# Peripheral_Circuit_A.net
KiCad netlist of a schematic drawn in Altium Designer
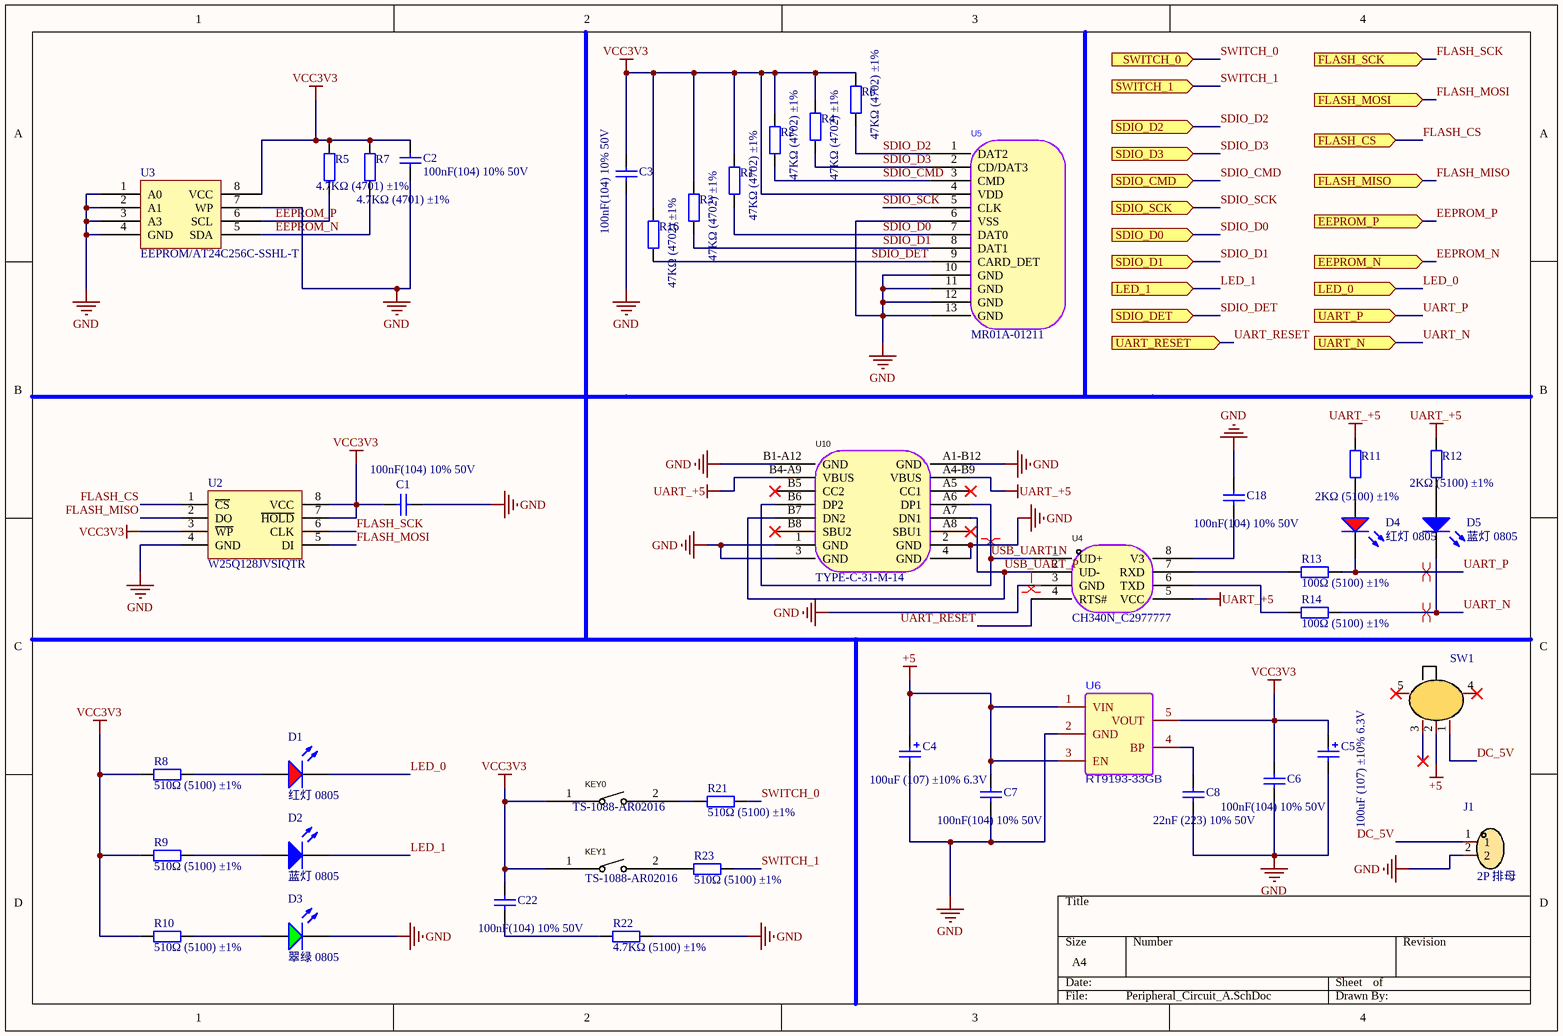
[diagram p0: Peripheral_Circuit_A.SchDoc]

(export (version "E")
  (design (tool "Eeschema 10.0.6"))
  (components
    (comp (ref "C1")
      (value "100nF(104) 10% 50V")
      (footprint "0805_C")
      (description "贴片电容")
      (libsource (lib "Miscellaneous Devices LC") (part "0805 100nF(104) 10% 50V"))
    )
    (comp (ref "C2")
      (value "100nF(104) 10% 50V")
      (footprint "0805_C")
      (description "贴片电容")
      (libsource (lib "Miscellaneous Devices LC") (part "0805 100nF(104) 10% 50V"))
    )
    (comp (ref "C3")
      (value "100nF(104) 10% 50V")
      (footprint "0805_C")
      (description "贴片电容")
      (libsource (lib "Miscellaneous Devices LC") (part "0805 100nF(104) 10% 50V"))
    )
    (comp (ref "C4")
      (value "100uF (107) ±10% 6.3V")
      (footprint "CASE-B_3528")
      (description "钽电容")
      (libsource (lib "Miscellaneous Devices LC") (part "3528 100uF (107) 10% 6.3V"))
    )
    (comp (ref "C5")
      (value "100uF (107) ±10% 6.3V")
      (footprint "CASE-B_3528")
      (description "钽电容")
      (libsource (lib "Miscellaneous Devices LC") (part "3528 100uF (107) 10% 6.3V"))
    )
    (comp (ref "C6")
      (value "100nF(104) 10% 50V")
      (footprint "0805_C")
      (description "贴片电容")
      (libsource (lib "Miscellaneous Devices LC") (part "0805 100nF(104) 10% 50V"))
    )
    (comp (ref "C7")
      (value "100nF(104) 10% 50V")
      (footprint "0805_C")
      (description "贴片电容")
      (libsource (lib "Miscellaneous Devices LC") (part "0805 100nF(104) 10% 50V"))
    )
    (comp (ref "C8")
      (value "22nF (223) 10% 50V")
      (footprint "0805_C")
      (description "贴片电容")
      (libsource (lib "Miscellaneous Devices LC") (part "0805 22nF (223) 10% 50V"))
    )
    (comp (ref "C18")
      (value "100nF(104) 10% 50V")
      (footprint "0805_C")
      (description "贴片电容")
      (libsource (lib "Miscellaneous Devices LC") (part "0805 100nF(104) 10% 50V"))
    )
    (comp (ref "C22")
      (value "100nF(104) 10% 50V")
      (footprint "0805_C")
      (description "贴片电容")
      (libsource (lib "Miscellaneous Devices LC") (part "0805 100nF(104) 10% 50V"))
    )
    (comp (ref "D1")
      (value "红灯 0805")
      (footprint "0805_LED_S1")
      (description "发光二极管")
      (libsource (lib "LED") (part "0805 红灯"))
    )
    (comp (ref "D2")
      (value "蓝灯 0805")
      (footprint "0805_LED_S1")
      (description "发光二极管")
      (libsource (lib "LED") (part "0805 蓝灯"))
    )
    (comp (ref "D3")
      (value "翠绿 0805")
      (footprint "0805_LED_S1")
      (description "发光二极管")
      (libsource (lib "LED") (part "0805 翠绿"))
    )
    (comp (ref "D4")
      (value "红灯 0805")
      (footprint "0805_LED_S1")
      (description "发光二极管")
      (libsource (lib "LED") (part "0805 红灯"))
    )
    (comp (ref "D5")
      (value "蓝灯 0805")
      (footprint "0805_LED_S1")
      (description "发光二极管")
      (libsource (lib "LED") (part "0805 蓝灯"))
    )
    (comp (ref "J1")
      (value "2P 排母")
      (footprint "PM254-1-02-W-8.5")
      (description "2p弯针")
      (fields
        (field (name "MANUFACTURER") "HCTL(华灿天禄)")
        (field (name "MANUFACTURER PART") "PM254-1-02-W-8.5")
      )
      (libsource (lib "EXTRA") (part "PM254-1-02-W-8.5"))
    )
    (comp (ref "KEY0")
      (value "TS-1088-AR02016")
      (footprint "SW-SMD_L3.9-W3.0-P4.45")
      (description "轻触开关")
      (fields (field (name "MANUFACTURER") "XUNPU(讯普)"))
      (libsource (lib "EXTRA") (part "TS-1088-AR02016"))
    )
    (comp (ref "KEY1")
      (value "TS-1088-AR02016")
      (footprint "SW-SMD_L3.9-W3.0-P4.45")
      (description "轻触开关")
      (fields (field (name "MANUFACTURER") "XUNPU(讯普)"))
      (libsource (lib "EXTRA") (part "TS-1088-AR02016"))
    )
    (comp (ref "R1")
      (value "47KΩ (4702) ±1%")
      (footprint "0805_R")
      (description "贴片电阻")
      (libsource (lib "Miscellaneous Devices LC") (part "0805 47KΩ (4702) 1%"))
    )
    (comp (ref "R2")
      (value "47KΩ (4702) ±1%")
      (footprint "0805_R")
      (description "贴片电阻")
      (libsource (lib "Miscellaneous Devices LC") (part "0805 47KΩ (4702) 1%"))
    )
    (comp (ref "R3")
      (value "47KΩ (4702) ±1%")
      (footprint "0805_R")
      (description "贴片电阻")
      (libsource (lib "Miscellaneous Devices LC") (part "0805 47KΩ (4702) 1%"))
    )
    (comp (ref "R4")
      (value "47KΩ (4702) ±1%")
      (footprint "0805_R")
      (description "贴片电阻")
      (libsource (lib "Miscellaneous Devices LC") (part "0805 47KΩ (4702) 1%"))
    )
    (comp (ref "R5")
      (value "4.7KΩ (4701) ±1%")
      (footprint "0805_R")
      (description "贴片电阻")
      (libsource (lib "Miscellaneous Devices LC") (part "0805 4.7KΩ (4701) 1%"))
    )
    (comp (ref "R6")
      (value "47KΩ (4702) ±1%")
      (footprint "0805_R")
      (description "贴片电阻")
      (libsource (lib "Miscellaneous Devices LC") (part "0805 47KΩ (4702) 1%"))
    )
    (comp (ref "R7")
      (value "4.7KΩ (4701) ±1%")
      (footprint "0805_R")
      (description "贴片电阻")
      (libsource (lib "Miscellaneous Devices LC") (part "0805 4.7KΩ (4701) 1%"))
    )
    (comp (ref "R8")
      (value "510Ω (5100) ±1%")
      (footprint "0805_R")
      (description "贴片电阻")
      (libsource (lib "Miscellaneous Devices LC") (part "0805 510Ω (5100) 1%"))
    )
    (comp (ref "R9")
      (value "510Ω (5100) ±1%")
      (footprint "0805_R")
      (description "贴片电阻")
      (libsource (lib "Miscellaneous Devices LC") (part "0805 510Ω (5100) 1%"))
    )
    (comp (ref "R10")
      (value "510Ω (5100) ±1%")
      (footprint "0805_R")
      (description "贴片电阻")
      (libsource (lib "Miscellaneous Devices LC") (part "0805 510Ω (5100) 1%"))
    )
    (comp (ref "R11")
      (value "2KΩ (5100) ±1%")
      (footprint "0805_R")
      (description "贴片电阻")
      (libsource (lib "") (part "0805 510Ω (5100) 1%_2"))
    )
    (comp (ref "R12")
      (value "2KΩ (5100) ±1%")
      (footprint "0805_R")
      (description "贴片电阻")
      (libsource (lib "") (part "0805 510Ω (5100) 1%_2"))
    )
    (comp (ref "R13")
      (value "100Ω (5100) ±1%")
      (footprint "0805_R")
      (description "贴片电阻")
      (libsource (lib "Miscellaneous Devices LC") (part "0805 510Ω (5100) 1%"))
    )
    (comp (ref "R14")
      (value "100Ω (5100) ±1%")
      (footprint "0805_R")
      (description "贴片电阻")
      (libsource (lib "Miscellaneous Devices LC") (part "0805 510Ω (5100) 1%"))
    )
    (comp (ref "R16")
      (value "47KΩ (4702) ±1%")
      (footprint "0805_R")
      (description "贴片电阻")
      (libsource (lib "Miscellaneous Devices LC") (part "0805 47KΩ (4702) 1%"))
    )
    (comp (ref "R21")
      (value "510Ω (5100) ±1%")
      (footprint "0805_R")
      (description "贴片电阻")
      (libsource (lib "Miscellaneous Devices LC") (part "0805 510Ω (5100) 1%"))
    )
    (comp (ref "R22")
      (value "4.7KΩ (5100) ±1%")
      (footprint "0805_R")
      (description "贴片电阻")
      (libsource (lib "") (part "0805 510Ω (5100) 1%_1"))
    )
    (comp (ref "R23")
      (value "510Ω (5100) ±1%")
      (footprint "0805_R")
      (description "贴片电阻")
      (libsource (lib "Miscellaneous Devices LC") (part "0805 510Ω (5100) 1%"))
    )
    (comp (ref "SW1")
      (value "SS12D07VG3 087")
      (footprint "SS12D07VG3")
      (description "直插贴片开关")
      (fields (field (name "MANUFACTURER") "SHOU HAN(首韩)"))
      (libsource (lib "EXTRA") (part "SS12D07VG3 087"))
    )
    (comp (ref "U2")
      (value "W25Q128JVSIQTR")
      (footprint "CH340_N")
      (description "Flash ROM")
      (libsource (lib "IC") (part "W25Q128JVSIQTR_[C97521]"))
    )
    (comp (ref "U3")
      (value "EEPROM/AT24C256C-SSHL-T")
      (footprint "CH340_N")
      (description "EEPROM")
      (libsource (lib "IC") (part "EEPROM/AT24C256C-SSHL-T_[C6482]"))
    )
    (comp (ref "U4")
      (value "CH340N_C2977777")
      (footprint "CH340_N")
      (description "TTL串口phy")
      (fields (field (name "DESIGNER") "U?"))
      (libsource (lib "EXTRA") (part "CH340N_C2977777"))
    )
    (comp (ref "U5")
      (value "MR01A-01211")
      (footprint "TF-SMD_MR01A-01211")
      (fields (field (name "MANUFACTURER") "ATOM(爱特姆)"))
      (libsource (lib "EXTRA") (part "MR01A-01211"))
    )
    (comp (ref "U6")
      (value "RT9193-33GB")
      (footprint "RT9193-33GB")
      (libsource (lib "EXTRA") (part "RT9193-33GB"))
    )
    (comp (ref "U10")
      (value "TYPE-C-31-M-14")
      (footprint "TYPE-C-31-M-14")
      (description "type-c接口")
      (fields (field (name "MANUFACTURER") "韩国韩荣"))
      (libsource (lib "EXTRA") (part "TYPE-C-31-M-14_1"))
    )
  )
  (nets
    (net (code "1") (name "+5") (class "Default")
      (node (ref "C4") (pin "1") (pinfunction "1_1") (pintype "passive"))
      (node (ref "C7") (pin "2") (pinfunction "2_2") (pintype "passive"))
      (node (ref "SW1") (pin "2") (pinfunction "2_2") (pintype "passive"))
      (node (ref "U6") (pin "1") (pinfunction "VIN_1") (pintype "passive"))
      (node (ref "U6") (pin "3") (pinfunction "EN_3") (pintype "passive"))
    )
    (net (code "2") (name "/DC_5V") (class "Default")
      (node (ref "J1") (pin "1") (pinfunction "1_1") (pintype "passive"))
      (node (ref "SW1") (pin "1") (pinfunction "1_1") (pintype "passive"))
    )
    (net (code "3") (name "/EEPROM_N") (class "Default")
      (node (ref "R7") (pin "1") (pinfunction "1_1") (pintype "passive"))
      (node (ref "U3") (pin "5") (pinfunction "SDA_5") (pintype "passive"))
    )
    (net (code "4") (name "/EEPROM_P") (class "Default")
      (node (ref "R5") (pin "1") (pinfunction "1_1") (pintype "passive"))
      (node (ref "U3") (pin "6") (pinfunction "SCL_6") (pintype "passive"))
    )
    (net (code "5") (name "/FLASH_CS") (class "Default")
      (node (ref "U2") (pin "1") (pinfunction "~{CS}_1") (pintype "passive"))
    )
    (net (code "6") (name "/FLASH_MISO") (class "Default")
      (node (ref "U2") (pin "2") (pinfunction "DO_2") (pintype "passive"))
    )
    (net (code "7") (name "/FLASH_MOSI") (class "Default")
      (node (ref "U2") (pin "5") (pinfunction "DI_5") (pintype "passive"))
    )
    (net (code "8") (name "/FLASH_SCK") (class "Default")
      (node (ref "U2") (pin "6") (pinfunction "CLK_6") (pintype "passive"))
    )
    (net (code "9") (name "/LED_0") (class "Default")
      (node (ref "D1") (pin "K") (pinfunction "K_K") (pintype "passive"))
    )
    (net (code "10") (name "/LED_1") (class "Default")
      (node (ref "D2") (pin "K") (pinfunction "K_K") (pintype "passive"))
    )
    (net (code "11") (name "/SDIO_CMD") (class "Default")
      (node (ref "R2") (pin "1") (pinfunction "1_1") (pintype "passive"))
      (node (ref "U5") (pin "3") (pinfunction "CMD_3") (pintype "passive"))
    )
    (net (code "12") (name "/SDIO_D0") (class "Default")
      (node (ref "R1") (pin "1") (pinfunction "1_1") (pintype "passive"))
      (node (ref "U5") (pin "7") (pinfunction "DAT0_7") (pintype "passive"))
    )
    (net (code "13") (name "/SDIO_D1") (class "Default")
      (node (ref "R3") (pin "1") (pinfunction "1_1") (pintype "passive"))
      (node (ref "U5") (pin "8") (pinfunction "DAT1_8") (pintype "passive"))
    )
    (net (code "14") (name "/SDIO_D2") (class "Default")
      (node (ref "R6") (pin "1") (pinfunction "1_1") (pintype "passive"))
      (node (ref "U5") (pin "1") (pinfunction "DAT2_1") (pintype "passive"))
    )
    (net (code "15") (name "/SDIO_D3") (class "Default")
      (node (ref "R4") (pin "1") (pinfunction "1_1") (pintype "passive"))
      (node (ref "U5") (pin "2") (pinfunction "CD/DAT3_2") (pintype "passive"))
    )
    (net (code "16") (name "/SDIO_DET") (class "Default")
      (node (ref "R16") (pin "1") (pinfunction "1_1") (pintype "passive"))
      (node (ref "U5") (pin "9") (pinfunction "CARD_DET_9") (pintype "passive"))
    )
    (net (code "17") (name "/SDIO_SCK") (class "Default")
      (node (ref "U5") (pin "5") (pinfunction "CLK_5") (pintype "passive"))
    )
    (net (code "18") (name "/SWITCH_0") (class "Default")
      (node (ref "R21") (pin "2") (pinfunction "2_2") (pintype "passive"))
    )
    (net (code "19") (name "/SWITCH_1") (class "Default")
      (node (ref "R23") (pin "2") (pinfunction "2_2") (pintype "passive"))
    )
    (net (code "20") (name "/UART_N") (class "Default")
      (node (ref "D5") (pin "K") (pinfunction "K_K") (pintype "passive"))
      (node (ref "R14") (pin "2") (pinfunction "2_2") (pintype "passive"))
    )
    (net (code "21") (name "/UART_P") (class "Default")
      (node (ref "D4") (pin "K") (pinfunction "K_K") (pintype "passive"))
      (node (ref "R13") (pin "2") (pinfunction "2_2") (pintype "passive"))
    )
    (net (code "22") (name "/UART_RESET") (class "Default")
      (node (ref "U4") (pin "4") (pinfunction "RTS#_4") (pintype "passive"))
    )
    (net (code "23") (name "/USB_UART_N") (class "Default")
      (node (ref "U10") (pin "A6") (pinfunction "DP1_A6") (pintype "passive"))
      (node (ref "U10") (pin "B6") (pinfunction "DP2_B6") (pintype "passive"))
      (node (ref "U4") (pin "1") (pinfunction "UD+_1") (pintype "passive"))
    )
    (net (code "24") (name "/USB_UART_P") (class "Default")
      (node (ref "U10") (pin "A7") (pinfunction "DN1_A7") (pintype "passive"))
      (node (ref "U10") (pin "B7") (pinfunction "DN2_B7") (pintype "passive"))
      (node (ref "U4") (pin "2") (pinfunction "UD-_2") (pintype "passive"))
    )
    (net (code "25") (name "GND") (class "Default")
      (node (ref "C1") (pin "2") (pinfunction "2_2") (pintype "passive"))
      (node (ref "C18") (pin "1") (pinfunction "1_1") (pintype "passive"))
      (node (ref "C2") (pin "1") (pinfunction "1_1") (pintype "passive"))
      (node (ref "C3") (pin "1") (pinfunction "1_1") (pintype "passive"))
      (node (ref "C4") (pin "2") (pinfunction "2_2") (pintype "passive"))
      (node (ref "C5") (pin "2") (pinfunction "2_2") (pintype "passive"))
      (node (ref "C6") (pin "1") (pinfunction "1_1") (pintype "passive"))
      (node (ref "C7") (pin "1") (pinfunction "1_1") (pintype "passive"))
      (node (ref "C8") (pin "1") (pinfunction "1_1") (pintype "passive"))
      (node (ref "D3") (pin "K") (pinfunction "K_K") (pintype "passive"))
      (node (ref "J1") (pin "2") (pinfunction "2_2") (pintype "passive"))
      (node (ref "R22") (pin "1") (pinfunction "1_1") (pintype "passive"))
      (node (ref "U10") (pin "1") (pinfunction "GND_1") (pintype "passive"))
      (node (ref "U10") (pin "2") (pinfunction "GND_2") (pintype "passive"))
      (node (ref "U10") (pin "3") (pinfunction "GND_3") (pintype "passive"))
      (node (ref "U10") (pin "4") (pinfunction "GND_4") (pintype "passive"))
      (node (ref "U10") (pin "A1-B12") (pinfunction "GND_A1-B12") (pintype "passive"))
      (node (ref "U10") (pin "B1-A12") (pinfunction "GND_B1-A12") (pintype "passive"))
      (node (ref "U2") (pin "4") (pinfunction "GND_4") (pintype "passive"))
      (node (ref "U3") (pin "1") (pinfunction "A0_1") (pintype "passive"))
      (node (ref "U3") (pin "2") (pinfunction "A1_2") (pintype "passive"))
      (node (ref "U3") (pin "3") (pinfunction "A3_3") (pintype "passive"))
      (node (ref "U3") (pin "4") (pinfunction "GND_4") (pintype "passive"))
      (node (ref "U3") (pin "7") (pinfunction "WP_7") (pintype "passive"))
      (node (ref "U4") (pin "3") (pinfunction "GND_3") (pintype "passive"))
      (node (ref "U5") (pin "10") (pinfunction "GND_10") (pintype "passive"))
      (node (ref "U5") (pin "11") (pinfunction "GND_11") (pintype "passive"))
      (node (ref "U5") (pin "12") (pinfunction "GND_12") (pintype "passive"))
      (node (ref "U5") (pin "13") (pinfunction "GND_13") (pintype "passive"))
      (node (ref "U5") (pin "6") (pinfunction "VSS_6") (pintype "passive"))
      (node (ref "U6") (pin "2") (pinfunction "GND_2") (pintype "passive"))
    )
    (net (code "26") (name "Net-(C22-Pad1)") (class "Default")
      (node (ref "C22") (pin "1") (pinfunction "1_1") (pintype "passive"))
      (node (ref "R22") (pin "2") (pinfunction "2_2") (pintype "passive"))
    )
    (net (code "27") (name "Net-(D1-PadA)") (class "Default")
      (node (ref "D1") (pin "A") (pinfunction "A_A") (pintype "passive"))
      (node (ref "R8") (pin "2") (pinfunction "2_2") (pintype "passive"))
    )
    (net (code "28") (name "Net-(D2-PadA)") (class "Default")
      (node (ref "D2") (pin "A") (pinfunction "A_A") (pintype "passive"))
      (node (ref "R9") (pin "2") (pinfunction "2_2") (pintype "passive"))
    )
    (net (code "29") (name "Net-(D3-PadA)") (class "Default")
      (node (ref "D3") (pin "A") (pinfunction "A_A") (pintype "passive"))
      (node (ref "R10") (pin "2") (pinfunction "2_2") (pintype "passive"))
    )
    (net (code "30") (name "Net-(D4-PadA)") (class "Default")
      (node (ref "D4") (pin "A") (pinfunction "A_A") (pintype "passive"))
      (node (ref "R11") (pin "1") (pinfunction "1_1") (pintype "passive"))
    )
    (net (code "31") (name "Net-(D5-PadA)") (class "Default")
      (node (ref "D5") (pin "A") (pinfunction "A_A") (pintype "passive"))
      (node (ref "R12") (pin "1") (pinfunction "1_1") (pintype "passive"))
    )
    (net (code "32") (name "Net-(KEY0-Pad2)") (class "Default")
      (node (ref "KEY0") (pin "2") (pinfunction "2_2") (pintype "passive"))
      (node (ref "R21") (pin "1") (pinfunction "1_1") (pintype "passive"))
    )
    (net (code "33") (name "Net-(KEY1-Pad2)") (class "Default")
      (node (ref "KEY1") (pin "2") (pinfunction "2_2") (pintype "passive"))
      (node (ref "R23") (pin "1") (pinfunction "1_1") (pintype "passive"))
    )
    (net (code "34") (name "Net-(U4-RXD)") (class "Default")
      (node (ref "R13") (pin "1") (pinfunction "1_1") (pintype "passive"))
      (node (ref "U4") (pin "7") (pinfunction "RXD_7") (pintype "passive"))
    )
    (net (code "35") (name "Net-(U4-TXD)") (class "Default")
      (node (ref "R14") (pin "1") (pinfunction "1_1") (pintype "passive"))
      (node (ref "U4") (pin "6") (pinfunction "TXD_6") (pintype "passive"))
    )
    (net (code "36") (name "Net-(U4-V3)") (class "Default")
      (node (ref "C18") (pin "2") (pinfunction "2_2") (pintype "passive"))
      (node (ref "U4") (pin "8") (pinfunction "V3_8") (pintype "passive"))
    )
    (net (code "37") (name "Net-(U6-BP)") (class "Default")
      (node (ref "C8") (pin "2") (pinfunction "2_2") (pintype "passive"))
      (node (ref "U6") (pin "4") (pinfunction "BP_4") (pintype "passive"))
    )
    (net (code "38") (name "UART_+5") (class "Default")
      (node (ref "R11") (pin "2") (pinfunction "2_2") (pintype "passive"))
      (node (ref "R12") (pin "2") (pinfunction "2_2") (pintype "passive"))
      (node (ref "U10") (pin "A4-B9") (pinfunction "VBUS_A4-B9") (pintype "passive"))
      (node (ref "U10") (pin "B4-A9") (pinfunction "VBUS_B4-A9") (pintype "passive"))
      (node (ref "U4") (pin "5") (pinfunction "VCC_5") (pintype "passive"))
    )
    (net (code "39") (name "VCC3V3") (class "Default")
      (node (ref "C1") (pin "1") (pinfunction "1_1") (pintype "passive"))
      (node (ref "C2") (pin "2") (pinfunction "2_2") (pintype "passive"))
      (node (ref "C22") (pin "2") (pinfunction "2_2") (pintype "passive"))
      (node (ref "C3") (pin "2") (pinfunction "2_2") (pintype "passive"))
      (node (ref "C5") (pin "1") (pinfunction "1_1") (pintype "passive"))
      (node (ref "C6") (pin "2") (pinfunction "2_2") (pintype "passive"))
      (node (ref "KEY0") (pin "1") (pinfunction "1_1") (pintype "passive"))
      (node (ref "KEY1") (pin "1") (pinfunction "1_1") (pintype "passive"))
      (node (ref "R1") (pin "2") (pinfunction "2_2") (pintype "passive"))
      (node (ref "R10") (pin "1") (pinfunction "1_1") (pintype "passive"))
      (node (ref "R16") (pin "2") (pinfunction "2_2") (pintype "passive"))
      (node (ref "R2") (pin "2") (pinfunction "2_2") (pintype "passive"))
      (node (ref "R3") (pin "2") (pinfunction "2_2") (pintype "passive"))
      (node (ref "R4") (pin "2") (pinfunction "2_2") (pintype "passive"))
      (node (ref "R5") (pin "2") (pinfunction "2_2") (pintype "passive"))
      (node (ref "R6") (pin "2") (pinfunction "2_2") (pintype "passive"))
      (node (ref "R7") (pin "2") (pinfunction "2_2") (pintype "passive"))
      (node (ref "R8") (pin "1") (pinfunction "1_1") (pintype "passive"))
      (node (ref "R9") (pin "1") (pinfunction "1_1") (pintype "passive"))
      (node (ref "U2") (pin "3") (pinfunction "~{WP}_3") (pintype "passive"))
      (node (ref "U2") (pin "7") (pinfunction "~{HOLD}_7") (pintype "passive"))
      (node (ref "U2") (pin "8") (pinfunction "VCC_8") (pintype "passive"))
      (node (ref "U3") (pin "8") (pinfunction "VCC_8") (pintype "passive"))
      (node (ref "U5") (pin "4") (pinfunction "VDD_4") (pintype "passive"))
      (node (ref "U6") (pin "5") (pinfunction "VOUT_5") (pintype "passive"))
    )
    (net (code "40") (name "unconnected-(SW1-Pad3)") (class "Default")
      (node (ref "SW1") (pin "3") (pinfunction "3_3") (pintype "passive+no_connect"))
    )
    (net (code "41") (name "unconnected-(SW1-Pad4)") (class "Default")
      (node (ref "SW1") (pin "4") (pinfunction "4_4") (pintype "passive+no_connect"))
    )
    (net (code "42") (name "unconnected-(SW1-Pad5)") (class "Default")
      (node (ref "SW1") (pin "5") (pinfunction "5_5") (pintype "passive+no_connect"))
    )
    (net (code "43") (name "unconnected-(U10-CC1-PadA5)") (class "Default")
      (node (ref "U10") (pin "A5") (pinfunction "CC1_A5") (pintype "passive+no_connect"))
    )
    (net (code "44") (name "unconnected-(U10-CC2-PadB5)") (class "Default")
      (node (ref "U10") (pin "B5") (pinfunction "CC2_B5") (pintype "passive+no_connect"))
    )
    (net (code "45") (name "unconnected-(U10-SBU1-PadA8)") (class "Default")
      (node (ref "U10") (pin "A8") (pinfunction "SBU1_A8") (pintype "passive+no_connect"))
    )
    (net (code "46") (name "unconnected-(U10-SBU2-PadB8)") (class "Default")
      (node (ref "U10") (pin "B8") (pinfunction "SBU2_B8") (pintype "passive+no_connect"))
    )
  )
)
